# Main.net
KiCad netlist of a schematic drawn in Altium Designer
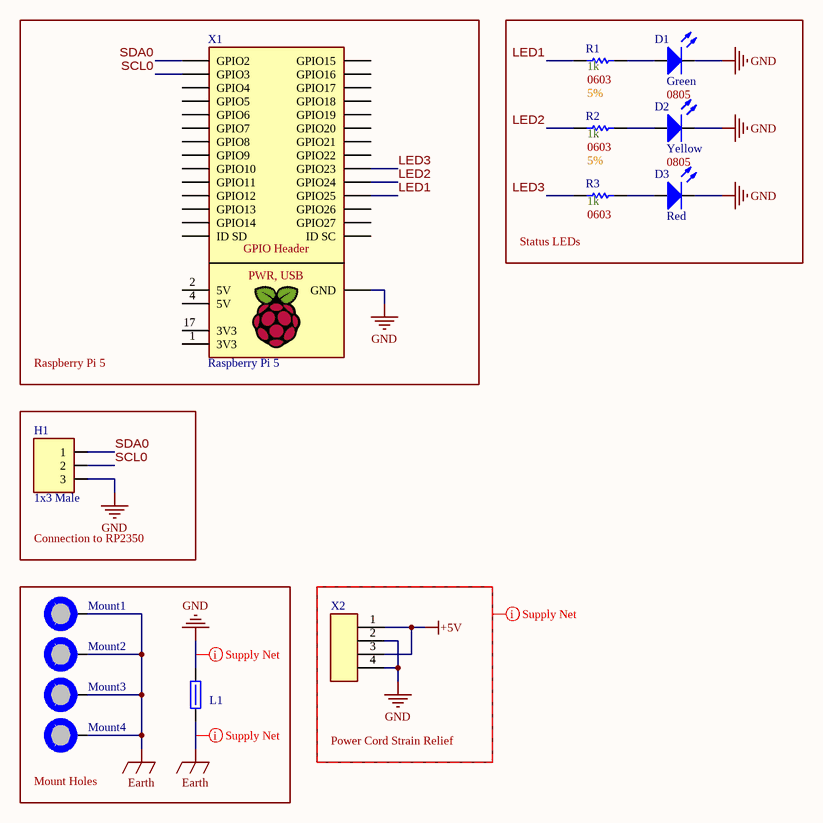
[diagram p0: Main.SchDoc]

(export (version "E")
  (design (tool "Eeschema 10.0.6"))
  (components
    (comp (ref "D1")
      (value "SMD LED")
      (footprint "[LED] SMD 0805")
      (description "Generic")
      (fields (field (name "COLOR") "Green") (field (name "SIZE PACKAGE") "0805"))
      (libsource (lib "RADM Components") (part "[LED] SMD"))
    )
    (comp (ref "D2")
      (value "SMD LED")
      (footprint "[LED] SMD 0805")
      (description "Generic")
      (fields (field (name "COLOR") "Yellow") (field (name "SIZE PACKAGE") "0805"))
      (libsource (lib "RADM Components") (part "[LED] SMD"))
    )
    (comp (ref "D3")
      (value "SMD LED")
      (footprint "[LED] SMD 0805")
      (description "Generic")
      (fields (field (name "COLOR") "Red"))
      (libsource (lib "RADM Components") (part "[LED] SMD"))
    )
    (comp (ref "H1")
      (value "1x3 Male")
      (footprint "[Header] Shrouded 1x3 Male")
      (description "070543-0037\r\nMates with 005057-9403")
      (libsource (lib "RADM Connectors") (part "[Header] Shrouded 1x3 Male"))
    )
    (comp (ref "L1")
      (value "652-MH2029-300Y")
      (footprint "[Ferrite] SMD Bead 0805 (1)")
      (libsource (lib "RADM Components") (part "[Ferrite] SMD Ferrite Bead (1)"))
    )
    (comp (ref "Mount1")
      (value "M3 Mount Hole")
      (footprint "[Mount] M3 Mount Hole")
      (description "Place at least 4.5mm from board edge. Plated.")
      (libsource (lib "RADM Connectors") (part "[Mount] M3 Mount Hole"))
    )
    (comp (ref "Mount2")
      (value "M3 Mount Hole")
      (footprint "[Mount] M3 Mount Hole")
      (description "Place at least 4.5mm from board edge. Plated.")
      (libsource (lib "RADM Connectors") (part "[Mount] M3 Mount Hole"))
    )
    (comp (ref "Mount3")
      (value "M3 Mount Hole")
      (footprint "[Mount] M3 Mount Hole")
      (description "Place at least 4.5mm from board edge. Plated.")
      (libsource (lib "RADM Connectors") (part "[Mount] M3 Mount Hole"))
    )
    (comp (ref "Mount4")
      (value "M3 Mount Hole")
      (footprint "[Mount] M3 Mount Hole")
      (description "Place at least 4.5mm from board edge. Plated.")
      (libsource (lib "RADM Connectors") (part "[Mount] M3 Mount Hole"))
    )
    (comp (ref "R1")
      (value "[Res] SMD Resistor")
      (footprint "[Res] SMD 0603")
      (description "Generic")
      (fields
        (field (name "RESISTANCE") "1k")
        (field (name "SIZE PACKAGE") "0603")
        (field (name "TOLERANCE") "5%")
      )
      (libsource (lib "RADM Components") (part "[Res] SMD Resistor"))
    )
    (comp (ref "R2")
      (value "[Res] SMD Resistor")
      (footprint "[Res] SMD 0603")
      (description "Generic")
      (fields
        (field (name "RESISTANCE") "1k")
        (field (name "SIZE PACKAGE") "0603")
        (field (name "TOLERANCE") "5%")
      )
      (libsource (lib "RADM Components") (part "[Res] SMD Resistor"))
    )
    (comp (ref "R3")
      (value "[Res] SMD Resistor")
      (footprint "[Res] SMD 0603")
      (description "Generic")
      (fields (field (name "RESISTANCE") "1k") (field (name "SIZE PACKAGE") "0603"))
      (libsource (lib "RADM Components") (part "[Res] SMD Resistor"))
    )
    (comp (ref "X1")
      (value "Raspberry Pi 5")
      (footprint "[Device] Raspberry Pi 5")
      (libsource (lib "RADM Components") (part "[Device] Raspberry Pi 5"))
    )
    (comp (ref "X2")
      (value "4pin Screw Terminal")
      (footprint "[Screw Terminal] 4pin 5mm")
      (libsource (lib "RADM Connectors") (part "[Screw Terminal] 4pin"))
    )
  )
  (nets
    (net (code "1") (name "+5V") (class "Default")
      (node (ref "X2") (pin "1") (pintype "power_in"))
      (node (ref "X2") (pin "3") (pintype "power_in"))
    )
    (net (code "2") (name "/LED1") (class "Default")
      (node (ref "R1") (pin "2") (pinfunction "2_2") (pintype "passive"))
      (node (ref "X1") (pin "22") (pinfunction "GPIO25_22") (pintype "passive"))
    )
    (net (code "3") (name "/LED2") (class "Default")
      (node (ref "R2") (pin "2") (pinfunction "2_2") (pintype "passive"))
      (node (ref "X1") (pin "18") (pinfunction "GPIO24_18") (pintype "passive"))
    )
    (net (code "4") (name "/LED3") (class "Default")
      (node (ref "R3") (pin "2") (pinfunction "2_2") (pintype "passive"))
      (node (ref "X1") (pin "16") (pinfunction "GPIO23_16") (pintype "passive"))
    )
    (net (code "5") (name "/SCL0") (class "Default")
      (node (ref "H1") (pin "2") (pinfunction "2_2") (pintype "passive"))
      (node (ref "X1") (pin "5") (pinfunction "GPIO3_5") (pintype "passive"))
    )
    (net (code "6") (name "/SDA0") (class "Default")
      (node (ref "H1") (pin "1") (pinfunction "1_1") (pintype "passive"))
      (node (ref "X1") (pin "3") (pinfunction "GPIO2_3") (pintype "passive"))
    )
    (net (code "7") (name "Earth") (class "Default")
      (node (ref "L1") (pin "1") (pinfunction "1_1") (pintype "passive"))
      (node (ref "Mount1") (pin "1") (pintype "power_in"))
      (node (ref "Mount2") (pin "1") (pintype "power_in"))
      (node (ref "Mount3") (pin "1") (pintype "power_in"))
      (node (ref "Mount4") (pin "1") (pintype "power_in"))
    )
    (net (code "8") (name "GND") (class "Default")
      (node (ref "D1") (pin "2") (pinfunction "Cathode_2") (pintype "passive"))
      (node (ref "D2") (pin "2") (pinfunction "Cathode_2") (pintype "passive"))
      (node (ref "D3") (pin "2") (pinfunction "Cathode_2") (pintype "passive"))
      (node (ref "H1") (pin "3") (pinfunction "3_3") (pintype "passive"))
      (node (ref "L1") (pin "2") (pinfunction "2_2") (pintype "passive"))
      (node (ref "X1") (pin "GND") (pinfunction "GND_GND") (pintype "passive"))
      (node (ref "X2") (pin "2") (pintype "power_in"))
      (node (ref "X2") (pin "4") (pintype "power_in"))
    )
    (net (code "9") (name "Net-(D1-Anode)") (class "Default")
      (node (ref "D1") (pin "1") (pinfunction "Anode_1") (pintype "passive"))
      (node (ref "R1") (pin "1") (pinfunction "1_1") (pintype "passive"))
    )
    (net (code "10") (name "Net-(D2-Anode)") (class "Default")
      (node (ref "D2") (pin "1") (pinfunction "Anode_1") (pintype "passive"))
      (node (ref "R2") (pin "1") (pinfunction "1_1") (pintype "passive"))
    )
    (net (code "11") (name "Net-(D3-Anode)") (class "Default")
      (node (ref "D3") (pin "1") (pinfunction "Anode_1") (pintype "passive"))
      (node (ref "R3") (pin "1") (pinfunction "1_1") (pintype "passive"))
    )
    (net (code "12") (name "unconnected-(X1-3V3-Pad1)") (class "Default")
      (node (ref "X1") (pin "1") (pinfunction "3V3_1") (pintype "passive"))
    )
    (net (code "13") (name "unconnected-(X1-3V3-Pad17)") (class "Default")
      (node (ref "X1") (pin "17") (pinfunction "3V3_17") (pintype "passive"))
    )
    (net (code "14") (name "unconnected-(X1-5V-Pad2)") (class "Default")
      (node (ref "X1") (pin "2") (pinfunction "5V_2") (pintype "passive"))
    )
    (net (code "15") (name "unconnected-(X1-5V-Pad4)") (class "Default")
      (node (ref "X1") (pin "4") (pinfunction "5V_4") (pintype "passive"))
    )
    (net (code "16") (name "unconnected-(X1-GPIO4-Pad7)") (class "Default")
      (node (ref "X1") (pin "7") (pinfunction "GPIO4_7") (pintype "passive"))
    )
    (net (code "17") (name "unconnected-(X1-GPIO5-Pad29)") (class "Default")
      (node (ref "X1") (pin "29") (pinfunction "GPIO5_29") (pintype "passive"))
    )
    (net (code "18") (name "unconnected-(X1-GPIO6-Pad31)") (class "Default")
      (node (ref "X1") (pin "31") (pinfunction "GPIO6_31") (pintype "passive"))
    )
    (net (code "19") (name "unconnected-(X1-GPIO7-Pad24)") (class "Default")
      (node (ref "X1") (pin "24") (pinfunction "GPIO7_24") (pintype "passive"))
    )
    (net (code "20") (name "unconnected-(X1-GPIO8-Pad26)") (class "Default")
      (node (ref "X1") (pin "26") (pinfunction "GPIO8_26") (pintype "passive"))
    )
    (net (code "21") (name "unconnected-(X1-GPIO9-Pad21)") (class "Default")
      (node (ref "X1") (pin "21") (pinfunction "GPIO9_21") (pintype "passive"))
    )
    (net (code "22") (name "unconnected-(X1-GPIO10-Pad19)") (class "Default")
      (node (ref "X1") (pin "19") (pinfunction "GPIO10_19") (pintype "passive"))
    )
    (net (code "23") (name "unconnected-(X1-GPIO11-Pad23)") (class "Default")
      (node (ref "X1") (pin "23") (pinfunction "GPIO11_23") (pintype "passive"))
    )
    (net (code "24") (name "unconnected-(X1-GPIO12-Pad32)") (class "Default")
      (node (ref "X1") (pin "32") (pinfunction "GPIO12_32") (pintype "passive"))
    )
    (net (code "25") (name "unconnected-(X1-GPIO13-Pad33)") (class "Default")
      (node (ref "X1") (pin "33") (pinfunction "GPIO13_33") (pintype "passive"))
    )
    (net (code "26") (name "unconnected-(X1-GPIO14-Pad8)") (class "Default")
      (node (ref "X1") (pin "8") (pinfunction "GPIO14_8") (pintype "passive"))
    )
    (net (code "27") (name "unconnected-(X1-GPIO15-Pad10)") (class "Default")
      (node (ref "X1") (pin "10") (pinfunction "GPIO15_10") (pintype "passive"))
    )
    (net (code "28") (name "unconnected-(X1-GPIO16-Pad36)") (class "Default")
      (node (ref "X1") (pin "36") (pinfunction "GPIO16_36") (pintype "passive"))
    )
    (net (code "29") (name "unconnected-(X1-GPIO17-Pad11)") (class "Default")
      (node (ref "X1") (pin "11") (pinfunction "GPIO17_11") (pintype "passive"))
    )
    (net (code "30") (name "unconnected-(X1-GPIO18-Pad12)") (class "Default")
      (node (ref "X1") (pin "12") (pinfunction "GPIO18_12") (pintype "passive"))
    )
    (net (code "31") (name "unconnected-(X1-GPIO19-Pad35)") (class "Default")
      (node (ref "X1") (pin "35") (pinfunction "GPIO19_35") (pintype "passive"))
    )
    (net (code "32") (name "unconnected-(X1-GPIO20-Pad38)") (class "Default")
      (node (ref "X1") (pin "38") (pinfunction "GPIO20_38") (pintype "passive"))
    )
    (net (code "33") (name "unconnected-(X1-GPIO21-Pad40)") (class "Default")
      (node (ref "X1") (pin "40") (pinfunction "GPIO21_40") (pintype "passive"))
    )
    (net (code "34") (name "unconnected-(X1-GPIO22-Pad15)") (class "Default")
      (node (ref "X1") (pin "15") (pinfunction "GPIO22_15") (pintype "passive"))
    )
    (net (code "35") (name "unconnected-(X1-GPIO26-Pad37)") (class "Default")
      (node (ref "X1") (pin "37") (pinfunction "GPIO26_37") (pintype "passive"))
    )
    (net (code "36") (name "unconnected-(X1-GPIO27-Pad13)") (class "Default")
      (node (ref "X1") (pin "13") (pinfunction "GPIO27_13") (pintype "passive"))
    )
    (net (code "37") (name "unconnected-(X1-ID_SC-Pad28)") (class "Default")
      (node (ref "X1") (pin "28") (pinfunction "ID_SC_28") (pintype "passive"))
    )
    (net (code "38") (name "unconnected-(X1-ID_SD-Pad27)") (class "Default")
      (node (ref "X1") (pin "27") (pinfunction "ID_SD_27") (pintype "passive"))
    )
  )
)
